# ic.net
KiCad netlist of a schematic drawn in Altium Designer
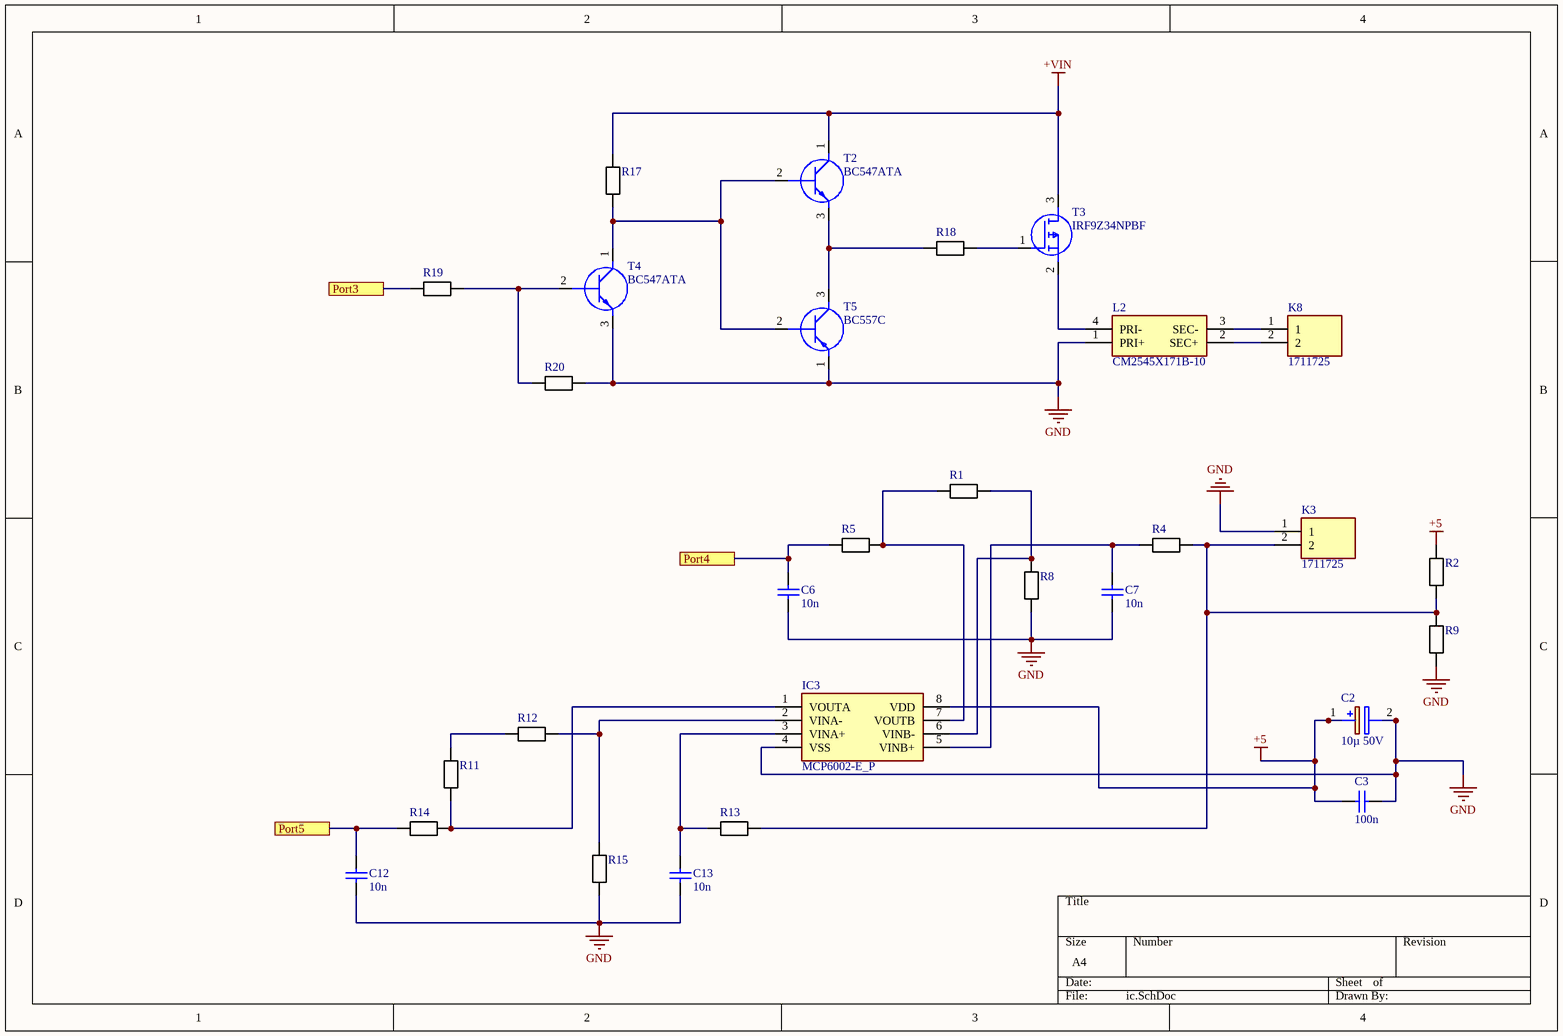
[diagram p0: ic.SchDoc]

(export (version "E")
  (design (tool "Eeschema 10.0.6"))
  (components
    (comp (ref "C2")
      (value "10µ 50V")
      (footprint "SamacSys:CAPPRD500W65D1025H1250")
      (description "Capacitor Polarised")
      (fields
        (field (name "MANUFACTURER_PART_NUMBER") "B41851A6227M000")
        (field (name "MOUSER PART NUMBER") "871-B41851A6227M000")
      )
      (libsource (lib "*") (part "B41851A6227M000"))
    )
    (comp (ref "C3")
      (value "100n")
      (footprint "LIBRARYSOURCE=Vault")
      (fields
        (field (name "PART NUMBER") "02015A270JAT2A")
        (field (name "MANUFACTURER") "AVX Interconnect / Elco")
      )
      (libsource (lib "Schlib1") (part "CAP"))
    )
    (comp (ref "C6")
      (value "10n")
      (footprint "LIBRARYSOURCE=Vault")
      (fields
        (field (name "PART NUMBER") "02015A270JAT2A")
        (field (name "MANUFACTURER") "AVX Interconnect / Elco")
      )
      (libsource (lib "Schlib1") (part "CAP"))
    )
    (comp (ref "C7")
      (value "10n")
      (footprint "LIBRARYSOURCE=Vault")
      (fields
        (field (name "PART NUMBER") "02015A270JAT2A")
        (field (name "MANUFACTURER") "AVX Interconnect / Elco")
      )
      (libsource (lib "Schlib1") (part "CAP"))
    )
    (comp (ref "C12")
      (value "10n")
      (footprint "LIBRARYSOURCE=Vault")
      (fields
        (field (name "PART NUMBER") "02015A270JAT2A")
        (field (name "MANUFACTURER") "AVX Interconnect / Elco")
      )
      (libsource (lib "Schlib1") (part "CAP"))
    )
    (comp (ref "C13")
      (value "10n")
      (footprint "LIBRARYSOURCE=Vault")
      (fields
        (field (name "PART NUMBER") "02015A270JAT2A")
        (field (name "MANUFACTURER") "AVX Interconnect / Elco")
      )
      (libsource (lib "Schlib1") (part "CAP"))
    )
    (comp (ref "IC3")
      (value "MCP6002-E_P")
      (footprint "SamacSys:DIP781W56P254L950H533Q8N")
      (description "Integrated Circuit")
      (fields
        (field (name "MANUFACTURER_PART_NUMBER") "MCP6002-E/P")
        (field (name "MOUSER PART NUMBER") "579-MCP6002-E/P")
      )
      (libsource (lib "Schlib1") (part "MCP6002-E_P"))
    )
    (comp (ref "K3")
      (value "1711725")
      (footprint "SamacSys:1711725")
      (description "Connector")
      (fields (field (name "MOUSER PART NUMBER") "651-1711725"))
      (libsource (lib "Schlib1") (part "1711725"))
    )
    (comp (ref "K8")
      (value "1711725")
      (footprint "SamacSys:1711725")
      (description "Connector")
      (fields (field (name "MOUSER PART NUMBER") "651-1711725"))
      (libsource (lib "Schlib1") (part "1711725"))
    )
    (comp (ref "L2")
      (value "CM2545X171B-10")
      (footprint "SamacSys:CM2545X171B10")
      (description "Transformer")
      (libsource (lib "*") (part "CM2545X171B-10"))
    )
    (comp (ref "R1")
      (value "CRCW08050000Z0EA")
      (footprint "RESC2012X65N")
      (fields (field (name "MANUFACTURER") "Vishay Dale"))
      (libsource (lib "Schlib1") (part "RES"))
    )
    (comp (ref "R2")
      (value "CRCW08050000Z0EA")
      (footprint "RESC2012X65N")
      (fields (field (name "MANUFACTURER") "Vishay Dale"))
      (libsource (lib "Schlib1") (part "RES"))
    )
    (comp (ref "R4")
      (value "CRCW08050000Z0EA")
      (footprint "RESC2012X65N")
      (fields (field (name "MANUFACTURER") "Vishay Dale"))
      (libsource (lib "Schlib1") (part "RES"))
    )
    (comp (ref "R5")
      (value "CRCW08050000Z0EA")
      (footprint "RESC2012X65N")
      (fields (field (name "MANUFACTURER") "Vishay Dale"))
      (libsource (lib "Schlib1") (part "RES"))
    )
    (comp (ref "R8")
      (value "CRCW08050000Z0EA")
      (footprint "RESC2012X65N")
      (fields (field (name "MANUFACTURER") "Vishay Dale"))
      (libsource (lib "Schlib1") (part "RES"))
    )
    (comp (ref "R9")
      (value "CRCW08050000Z0EA")
      (footprint "RESC2012X65N")
      (fields (field (name "MANUFACTURER") "Vishay Dale"))
      (libsource (lib "Schlib1") (part "RES"))
    )
    (comp (ref "R11")
      (value "CRCW08050000Z0EA")
      (footprint "RESC2012X65N")
      (fields (field (name "MANUFACTURER") "Vishay Dale"))
      (libsource (lib "Schlib1") (part "RES"))
    )
    (comp (ref "R12")
      (value "CRCW08050000Z0EA")
      (footprint "RESC2012X65N")
      (fields (field (name "MANUFACTURER") "Vishay Dale"))
      (libsource (lib "Schlib1") (part "RES"))
    )
    (comp (ref "R13")
      (value "CRCW08050000Z0EA")
      (footprint "RESC2012X65N")
      (fields (field (name "MANUFACTURER") "Vishay Dale"))
      (libsource (lib "Schlib1") (part "RES"))
    )
    (comp (ref "R14")
      (value "CRCW08050000Z0EA")
      (footprint "RESC2012X65N")
      (fields (field (name "MANUFACTURER") "Vishay Dale"))
      (libsource (lib "Schlib1") (part "RES"))
    )
    (comp (ref "R15")
      (value "CRCW08050000Z0EA")
      (footprint "RESC2012X65N")
      (fields (field (name "MANUFACTURER") "Vishay Dale"))
      (libsource (lib "Schlib1") (part "RES"))
    )
    (comp (ref "R17")
      (value "CRCW08050000Z0EA")
      (footprint "RESC2012X65N")
      (fields (field (name "MANUFACTURER") "Vishay Dale"))
      (libsource (lib "Schlib1") (part "RES"))
    )
    (comp (ref "R18")
      (value "CRCW08050000Z0EA")
      (footprint "RESC2012X65N")
      (fields (field (name "MANUFACTURER") "Vishay Dale"))
      (libsource (lib "Schlib1") (part "RES"))
    )
    (comp (ref "R19")
      (value "CRCW08050000Z0EA")
      (footprint "RESC2012X65N")
      (fields (field (name "MANUFACTURER") "Vishay Dale"))
      (libsource (lib "Schlib1") (part "RES"))
    )
    (comp (ref "R20")
      (value "CRCW08050000Z0EA")
      (footprint "RESC2012X65N")
      (fields (field (name "MANUFACTURER") "Vishay Dale"))
      (libsource (lib "Schlib1") (part "RES"))
    )
    (comp (ref "T2")
      (value "BC547ATA")
      (footprint "SamacSys:TO-92_(TO-226)")
      (description "Transistor BJT NPN")
      (fields (field (name "MOUSER PART NUMBER") "512-BC547ATA"))
      (libsource (lib "Schlib1") (part "BC547ATA"))
    )
    (comp (ref "T3")
      (value "IRF9Z34NPBF")
      (footprint "SamacSys:TO254P469X1042X1967-3P")
      (description "MOSFET (P-Channel)")
      (fields (field (name "MOUSER PART NUMBER") "942-IRF9Z34NPBF"))
      (libsource (lib "Schlib1") (part "IRF9Z34NPBF"))
    )
    (comp (ref "T4")
      (value "BC547ATA")
      (footprint "SamacSys:TO-92_(TO-226)")
      (description "Transistor BJT NPN")
      (fields (field (name "MOUSER PART NUMBER") "512-BC547ATA"))
      (libsource (lib "Schlib1") (part "BC547ATA"))
    )
    (comp (ref "T5")
      (value "BC557C")
      (footprint "SamacSys:BC557C")
      (description "Transistor BJT PNP")
      (fields (field (name "MOUSER PART NUMBER") "771-BC557C"))
      (libsource (lib "Schlib1") (part "BC557C"))
    )
  )
  (nets
    (net (code "1") (name "+5") (class "Default")
      (node (ref "C2") (pin "1") (pinfunction "+_1") (pintype "passive"))
      (node (ref "C3") (pin "1") (pinfunction "1_1") (pintype "passive"))
      (node (ref "IC3") (pin "8") (pinfunction "VDD_8") (pintype "passive"))
      (node (ref "R2") (pin "2") (pinfunction "2_2") (pintype "passive"))
    )
    (net (code "2") (name "+VIN") (class "Default")
      (node (ref "R17") (pin "2") (pinfunction "2_2") (pintype "passive"))
      (node (ref "T2") (pin "1") (pinfunction "C_1") (pintype "passive"))
      (node (ref "T3") (pin "3") (pinfunction "D_3") (pintype "passive"))
    )
    (net (code "3") (name "/Port3") (class "Default")
      (node (ref "R19") (pin "1") (pinfunction "1_1") (pintype "passive"))
    )
    (net (code "4") (name "/Port4") (class "Default")
      (node (ref "C6") (pin "2") (pinfunction "2_2") (pintype "passive"))
      (node (ref "R5") (pin "1") (pinfunction "1_1") (pintype "passive"))
    )
    (net (code "5") (name "/Port5") (class "Default")
      (node (ref "C12") (pin "2") (pinfunction "2_2") (pintype "passive"))
      (node (ref "R14") (pin "1") (pinfunction "1_1") (pintype "passive"))
    )
    (net (code "6") (name "GND") (class "Default")
      (node (ref "C12") (pin "1") (pinfunction "1_1") (pintype "passive"))
      (node (ref "C13") (pin "1") (pinfunction "1_1") (pintype "passive"))
      (node (ref "C2") (pin "2") (pinfunction "-_2") (pintype "passive"))
      (node (ref "C3") (pin "2") (pinfunction "2_2") (pintype "passive"))
      (node (ref "C6") (pin "1") (pinfunction "1_1") (pintype "passive"))
      (node (ref "C7") (pin "1") (pinfunction "1_1") (pintype "passive"))
      (node (ref "IC3") (pin "4") (pinfunction "VSS_4") (pintype "passive"))
      (node (ref "K3") (pin "1") (pinfunction "1_1") (pintype "passive"))
      (node (ref "L2") (pin "1") (pinfunction "PRI+_1") (pintype "passive"))
      (node (ref "R15") (pin "1") (pinfunction "1_1") (pintype "passive"))
      (node (ref "R20") (pin "2") (pinfunction "2_2") (pintype "passive"))
      (node (ref "R8") (pin "1") (pinfunction "1_1") (pintype "passive"))
      (node (ref "R9") (pin "1") (pinfunction "1_1") (pintype "passive"))
      (node (ref "T4") (pin "3") (pinfunction "E_3") (pintype "passive"))
      (node (ref "T5") (pin "1") (pinfunction "E_1") (pintype "passive"))
    )
    (net (code "7") (name "Net-(IC3-VINA+)") (class "Default")
      (node (ref "C13") (pin "2") (pinfunction "2_2") (pintype "passive"))
      (node (ref "IC3") (pin "3") (pinfunction "VINA+_3") (pintype "passive"))
      (node (ref "R13") (pin "1") (pinfunction "1_1") (pintype "passive"))
    )
    (net (code "8") (name "Net-(IC3-VINA-)") (class "Default")
      (node (ref "IC3") (pin "2") (pinfunction "VINA-_2") (pintype "passive"))
      (node (ref "R12") (pin "2") (pinfunction "2_2") (pintype "passive"))
      (node (ref "R15") (pin "2") (pinfunction "2_2") (pintype "passive"))
    )
    (net (code "9") (name "Net-(IC3-VINB+)") (class "Default")
      (node (ref "C7") (pin "2") (pinfunction "2_2") (pintype "passive"))
      (node (ref "IC3") (pin "5") (pinfunction "VINB+_5") (pintype "passive"))
      (node (ref "R4") (pin "1") (pinfunction "1_1") (pintype "passive"))
    )
    (net (code "10") (name "Net-(IC3-VINB-)") (class "Default")
      (node (ref "IC3") (pin "6") (pinfunction "VINB-_6") (pintype "passive"))
      (node (ref "R1") (pin "2") (pinfunction "2_2") (pintype "passive"))
      (node (ref "R8") (pin "2") (pinfunction "2_2") (pintype "passive"))
    )
    (net (code "11") (name "Net-(IC3-VOUTA)") (class "Default")
      (node (ref "IC3") (pin "1") (pinfunction "VOUTA_1") (pintype "passive"))
      (node (ref "R11") (pin "1") (pinfunction "1_1") (pintype "passive"))
      (node (ref "R14") (pin "2") (pinfunction "2_2") (pintype "passive"))
    )
    (net (code "12") (name "Net-(IC3-VOUTB)") (class "Default")
      (node (ref "IC3") (pin "7") (pinfunction "VOUTB_7") (pintype "passive"))
      (node (ref "R1") (pin "1") (pinfunction "1_1") (pintype "passive"))
      (node (ref "R5") (pin "2") (pinfunction "2_2") (pintype "passive"))
    )
    (net (code "13") (name "Net-(K3-Pad2)") (class "Default")
      (node (ref "K3") (pin "2") (pinfunction "2_2") (pintype "passive"))
      (node (ref "R13") (pin "2") (pinfunction "2_2") (pintype "passive"))
      (node (ref "R2") (pin "1") (pinfunction "1_1") (pintype "passive"))
      (node (ref "R4") (pin "2") (pinfunction "2_2") (pintype "passive"))
      (node (ref "R9") (pin "2") (pinfunction "2_2") (pintype "passive"))
    )
    (net (code "14") (name "Net-(L2-PRI-)") (class "Default")
      (node (ref "L2") (pin "4") (pinfunction "PRI-_4") (pintype "passive"))
      (node (ref "T3") (pin "2") (pinfunction "S_2") (pintype "passive"))
    )
    (net (code "15") (name "Net-(L2-SEC+)") (class "Default")
      (node (ref "K8") (pin "2") (pinfunction "2_2") (pintype "passive"))
      (node (ref "L2") (pin "2") (pinfunction "SEC+_2") (pintype "passive"))
    )
    (net (code "16") (name "Net-(L2-SEC-)") (class "Default")
      (node (ref "K8") (pin "1") (pinfunction "1_1") (pintype "passive"))
      (node (ref "L2") (pin "3") (pinfunction "SEC-_3") (pintype "passive"))
    )
    (net (code "17") (name "Net-(R11-Pad2)") (class "Default")
      (node (ref "R11") (pin "2") (pinfunction "2_2") (pintype "passive"))
      (node (ref "R12") (pin "1") (pinfunction "1_1") (pintype "passive"))
    )
    (net (code "18") (name "Net-(T2-B)") (class "Default")
      (node (ref "R17") (pin "1") (pinfunction "1_1") (pintype "passive"))
      (node (ref "T2") (pin "2") (pinfunction "B_2") (pintype "passive"))
      (node (ref "T4") (pin "1") (pinfunction "C_1") (pintype "passive"))
      (node (ref "T5") (pin "2") (pinfunction "B_2") (pintype "passive"))
    )
    (net (code "19") (name "Net-(T2-E)") (class "Default")
      (node (ref "R18") (pin "1") (pinfunction "1_1") (pintype "passive"))
      (node (ref "T2") (pin "3") (pinfunction "E_3") (pintype "passive"))
      (node (ref "T5") (pin "3") (pinfunction "C_3") (pintype "passive"))
    )
    (net (code "20") (name "Net-(T3-G)") (class "Default")
      (node (ref "R18") (pin "2") (pinfunction "2_2") (pintype "passive"))
      (node (ref "T3") (pin "1") (pinfunction "G_1") (pintype "passive"))
    )
    (net (code "21") (name "Net-(T4-B)") (class "Default")
      (node (ref "R19") (pin "2") (pinfunction "2_2") (pintype "passive"))
      (node (ref "R20") (pin "1") (pinfunction "1_1") (pintype "passive"))
      (node (ref "T4") (pin "2") (pinfunction "B_2") (pintype "passive"))
    )
  )
)
